# opencoral_moonlight.net
KiCad netlist of a schematic drawn in EAGLE
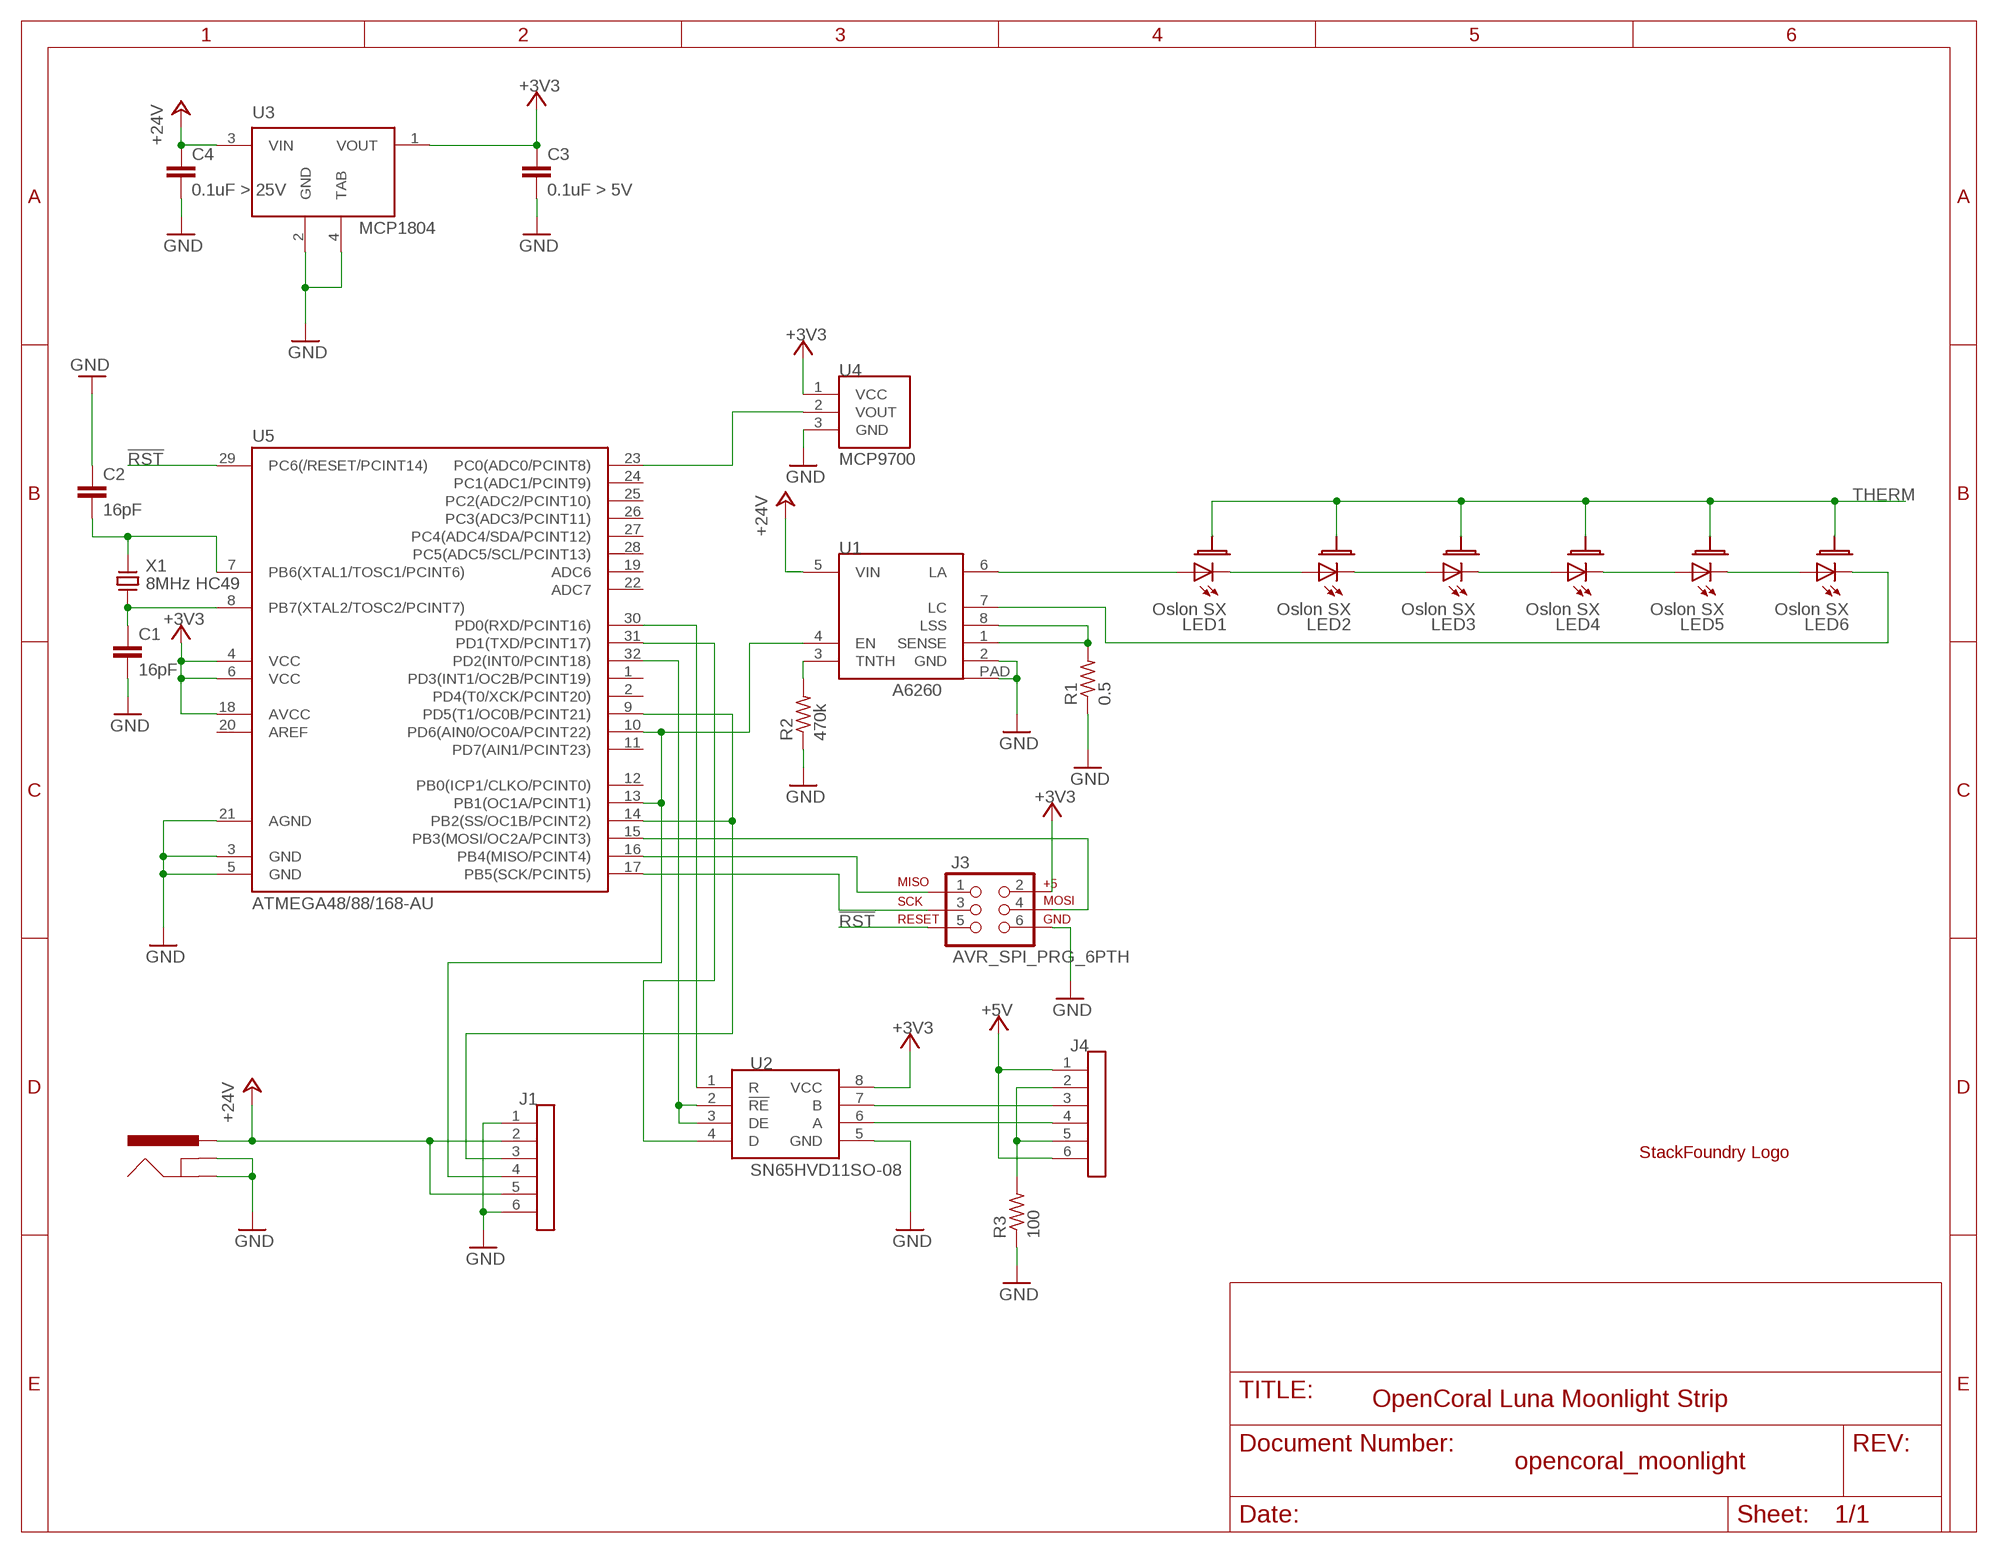
[diagram p0: schematic, sheet 1]

(export (version "E")
  (design (tool "Eeschema 10.0.6"))
  (components
    (comp (ref "C1")
      (value "16pF")
      (footprint "eagle-import:C0603")
      (libsource (lib "eagle-import") (part "C-EUC0603"))
    )
    (comp (ref "C2")
      (value "16pF")
      (footprint "eagle-import:C0603")
      (libsource (lib "eagle-import") (part "C-EUC0603"))
    )
    (comp (ref "C3")
      (value "0.1uF > 5V")
      (footprint "eagle-import:C0603")
      (libsource (lib "eagle-import") (part "C-EUC0603"))
    )
    (comp (ref "C4")
      (value "0.1uF > 25V")
      (footprint "eagle-import:C0603")
      (libsource (lib "eagle-import") (part "C-EUC0603"))
    )
    (comp (ref "J1")
      (value "RJ12")
      (footprint "eagle-import:A-2004-RJ12")
      (libsource (lib "eagle-import") (part "RJ12"))
    )
    (comp (ref "J2")
      (value "POWER_JACKPTH")
      (footprint "eagle-import:POWER_JACK_PTH")
      (libsource (lib "eagle-import") (part "POWER_JACKPTH"))
    )
    (comp (ref "J3")
      (value "AVR_SPI_PRG_6PTH")
      (footprint "eagle-import:2X3")
      (libsource (lib "eagle-import") (part "AVR_SPI_PRG_6PTH"))
    )
    (comp (ref "J4")
      (value "RJ12")
      (footprint "eagle-import:A-2004-RJ12")
      (libsource (lib "eagle-import") (part "RJ12"))
    )
    (comp (ref "LED1")
      (value "Oslon SX")
      (footprint "eagle-import:OSRAM_OSLON_SX")
      (libsource (lib "eagle-import") (part "LEDOSLON_SX"))
    )
    (comp (ref "LED2")
      (value "Oslon SX")
      (footprint "eagle-import:OSRAM_OSLON_SX")
      (libsource (lib "eagle-import") (part "LEDOSLON_SX"))
    )
    (comp (ref "LED3")
      (value "Oslon SX")
      (footprint "eagle-import:OSRAM_OSLON_SX")
      (libsource (lib "eagle-import") (part "LEDOSLON_SX"))
    )
    (comp (ref "LED4")
      (value "Oslon SX")
      (footprint "eagle-import:OSRAM_OSLON_SX")
      (libsource (lib "eagle-import") (part "LEDOSLON_SX"))
    )
    (comp (ref "LED5")
      (value "Oslon SX")
      (footprint "eagle-import:OSRAM_OSLON_SX")
      (libsource (lib "eagle-import") (part "LEDOSLON_SX"))
    )
    (comp (ref "LED6")
      (value "Oslon SX")
      (footprint "eagle-import:OSRAM_OSLON_SX")
      (libsource (lib "eagle-import") (part "LEDOSLON_SX"))
    )
    (comp (ref "LOGO1")
      (value "SFLOGO")
      (footprint "eagle-import:SFLOGO")
      (libsource (lib "eagle-import") (part "SFLOGO"))
    )
    (comp (ref "R1")
      (value "0.5")
      (footprint "eagle-import:R0805")
      (libsource (lib "eagle-import") (part "R-US_R0805"))
    )
    (comp (ref "R2")
      (value "470k")
      (footprint "eagle-import:R0603")
      (libsource (lib "eagle-import") (part "R-US_R0603"))
    )
    (comp (ref "R3")
      (value "100")
      (footprint "eagle-import:R0603")
      (libsource (lib "eagle-import") (part "R-US_R0603"))
    )
    (comp (ref "U1")
      (value "A6260")
      (footprint "eagle-import:ESOIC-8")
      (libsource (lib "eagle-import") (part "A6260"))
    )
    (comp (ref "U2")
      (value "SN65HVD11SO-08")
      (footprint "eagle-import:SO-08")
      (libsource (lib "eagle-import") (part "SN65HVD11SO-08"))
    )
    (comp (ref "U3")
      (value "MCP1804")
      (footprint "eagle-import:SOT223-3")
      (libsource (lib "eagle-import") (part "MCP1804"))
    )
    (comp (ref "U4")
      (value "MCP9700")
      (footprint "eagle-import:SOT23")
      (libsource (lib "eagle-import") (part "MCP9700"))
    )
    (comp (ref "U5")
      (value "ATMEGA48/88/168-AU")
      (footprint "eagle-import:TQFP32-08")
      (libsource (lib "eagle-import") (part "ATMEGA48/88/168-AU"))
    )
    (comp (ref "X1")
      (value "8MHz HC49")
      (footprint "eagle-import:HCM49")
      (libsource (lib "eagle-import") (part "HCM49_18.432M"))
    )
  )
  (nets
    (net (code "1") (name "+3V3") (class "Default")
      (node (ref "C3") (pin "1") (pinfunction "1_1") (pintype "passive"))
      (node (ref "J3") (pin "2") (pinfunction "2_2") (pintype "passive"))
      (node (ref "U2") (pin "8") (pinfunction "VCC_8") (pintype "bidirectional"))
      (node (ref "U3") (pin "1") (pinfunction "VOUT_1") (pintype "bidirectional"))
      (node (ref "U4") (pin "1") (pinfunction "VCC_1") (pintype "bidirectional"))
      (node (ref "U5") (pin "18") (pinfunction "AVCC_18") (pintype "passive"))
      (node (ref "U5") (pin "4") (pinfunction "VCC_4") (pintype "power_in"))
      (node (ref "U5") (pin "6") (pinfunction "VCC_6") (pintype "power_in"))
    )
    (net (code "2") (name "+5V") (class "Default")
      (node (ref "J4") (pin "1") (pinfunction "P$1_1") (pintype "bidirectional"))
      (node (ref "J4") (pin "6") (pinfunction "P$6_6") (pintype "bidirectional"))
    )
    (net (code "3") (name "+24V") (class "Default")
      (node (ref "C4") (pin "1") (pinfunction "1_1") (pintype "passive"))
      (node (ref "J1") (pin "2") (pinfunction "P$2_2") (pintype "bidirectional"))
      (node (ref "J1") (pin "5") (pinfunction "P$5_5") (pintype "bidirectional"))
      (node (ref "J2") (pin "PWR") (pinfunction "PWR_PWR") (pintype "bidirectional"))
      (node (ref "U1") (pin "5") (pinfunction "VIN_5") (pintype "bidirectional"))
      (node (ref "U3") (pin "3") (pinfunction "VIN_3") (pintype "bidirectional"))
    )
    (net (code "4") (name "/THERM") (class "Default")
      (node (ref "LED1") (pin "THERM") (pinfunction "THERM_THERM") (pintype "bidirectional"))
      (node (ref "LED2") (pin "THERM") (pinfunction "THERM_THERM") (pintype "bidirectional"))
      (node (ref "LED3") (pin "THERM") (pinfunction "THERM_THERM") (pintype "bidirectional"))
      (node (ref "LED4") (pin "THERM") (pinfunction "THERM_THERM") (pintype "bidirectional"))
      (node (ref "LED5") (pin "THERM") (pinfunction "THERM_THERM") (pintype "bidirectional"))
      (node (ref "LED6") (pin "THERM") (pinfunction "THERM_THERM") (pintype "bidirectional"))
    )
    (net (code "5") (name "/~{RST}") (class "Default")
      (node (ref "J3") (pin "5") (pinfunction "5_5") (pintype "passive"))
      (node (ref "U5") (pin "29") (pinfunction "PC6(/RESET/PCINT14)_29") (pintype "bidirectional"))
    )
    (net (code "6") (name "GND") (class "Default")
      (node (ref "C1") (pin "2") (pinfunction "2_2") (pintype "passive"))
      (node (ref "C2") (pin "1") (pinfunction "1_1") (pintype "passive"))
      (node (ref "C3") (pin "2") (pinfunction "2_2") (pintype "passive"))
      (node (ref "C4") (pin "2") (pinfunction "2_2") (pintype "passive"))
      (node (ref "J1") (pin "1") (pinfunction "P$1_1") (pintype "bidirectional"))
      (node (ref "J1") (pin "6") (pinfunction "P$6_6") (pintype "bidirectional"))
      (node (ref "J2") (pin "GND") (pinfunction "GND_GND") (pintype "bidirectional"))
      (node (ref "J2") (pin "GNDBREAK") (pinfunction "GNDBREAK_GNDBREAK") (pintype "bidirectional"))
      (node (ref "J3") (pin "6") (pinfunction "6_6") (pintype "passive"))
      (node (ref "R1") (pin "1") (pinfunction "1_1") (pintype "passive"))
      (node (ref "R2") (pin "1") (pinfunction "1_1") (pintype "passive"))
      (node (ref "R3") (pin "1") (pinfunction "1_1") (pintype "passive"))
      (node (ref "U1") (pin "2") (pinfunction "GND_2") (pintype "bidirectional"))
      (node (ref "U1") (pin "PAD") (pinfunction "PAD_PAD") (pintype "bidirectional"))
      (node (ref "U2") (pin "5") (pinfunction "GND_5") (pintype "bidirectional"))
      (node (ref "U3") (pin "2") (pinfunction "GND_2") (pintype "bidirectional"))
      (node (ref "U3") (pin "4") (pinfunction "TAB_4") (pintype "bidirectional"))
      (node (ref "U4") (pin "3") (pinfunction "GND_3") (pintype "bidirectional"))
      (node (ref "U5") (pin "21") (pinfunction "AGND_21") (pintype "power_in"))
      (node (ref "U5") (pin "3") (pinfunction "GND_3") (pintype "power_in"))
      (node (ref "U5") (pin "5") (pinfunction "GND_5") (pintype "power_in"))
    )
    (net (code "7") (name "Net-(J1-P$3)") (class "Default")
      (node (ref "J1") (pin "3") (pinfunction "P$3_3") (pintype "bidirectional"))
      (node (ref "U5") (pin "14") (pinfunction "PB2(SS/OC1B/PCINT2)_14") (pintype "bidirectional"))
      (node (ref "U5") (pin "9") (pinfunction "PD5(T1/OC0B/PCINT21)_9") (pintype "bidirectional"))
    )
    (net (code "8") (name "Net-(J1-P$4)") (class "Default")
      (node (ref "J1") (pin "4") (pinfunction "P$4_4") (pintype "bidirectional"))
      (node (ref "U1") (pin "4") (pinfunction "EN_4") (pintype "bidirectional"))
      (node (ref "U5") (pin "10") (pinfunction "PD6(AIN0/OC0A/PCINT22)_10") (pintype "bidirectional"))
      (node (ref "U5") (pin "13") (pinfunction "PB1(OC1A/PCINT1)_13") (pintype "bidirectional"))
    )
    (net (code "9") (name "Net-(J4-P$2)") (class "Default")
      (node (ref "J4") (pin "2") (pinfunction "P$2_2") (pintype "bidirectional"))
      (node (ref "J4") (pin "5") (pinfunction "P$5_5") (pintype "bidirectional"))
      (node (ref "R3") (pin "2") (pinfunction "2_2") (pintype "passive"))
    )
    (net (code "10") (name "Net-(J4-P$3)") (class "Default")
      (node (ref "J4") (pin "3") (pinfunction "P$3_3") (pintype "bidirectional"))
      (node (ref "U2") (pin "7") (pinfunction "B_7") (pintype "bidirectional"))
    )
    (net (code "11") (name "Net-(J4-P$4)") (class "Default")
      (node (ref "J4") (pin "4") (pinfunction "P$4_4") (pintype "bidirectional"))
      (node (ref "U2") (pin "6") (pinfunction "A_6") (pintype "bidirectional"))
    )
    (net (code "12") (name "Net-(LED1-PadC)") (class "Default")
      (node (ref "LED1") (pin "C") (pinfunction "C_C") (pintype "passive"))
      (node (ref "LED2") (pin "A") (pinfunction "A_A") (pintype "passive"))
    )
    (net (code "13") (name "Net-(LED2-PadC)") (class "Default")
      (node (ref "LED2") (pin "C") (pinfunction "C_C") (pintype "passive"))
      (node (ref "LED3") (pin "A") (pinfunction "A_A") (pintype "passive"))
    )
    (net (code "14") (name "Net-(LED3-PadC)") (class "Default")
      (node (ref "LED3") (pin "C") (pinfunction "C_C") (pintype "passive"))
      (node (ref "LED4") (pin "A") (pinfunction "A_A") (pintype "passive"))
    )
    (net (code "15") (name "Net-(LED4-PadC)") (class "Default")
      (node (ref "LED4") (pin "C") (pinfunction "C_C") (pintype "passive"))
      (node (ref "LED5") (pin "A") (pinfunction "A_A") (pintype "passive"))
    )
    (net (code "16") (name "Net-(LED5-PadC)") (class "Default")
      (node (ref "LED5") (pin "C") (pinfunction "C_C") (pintype "passive"))
      (node (ref "LED6") (pin "A") (pinfunction "A_A") (pintype "passive"))
    )
    (net (code "17") (name "Net-(U1-LA)") (class "Default")
      (node (ref "LED1") (pin "A") (pinfunction "A_A") (pintype "passive"))
      (node (ref "U1") (pin "6") (pinfunction "LA_6") (pintype "bidirectional"))
    )
    (net (code "18") (name "Net-(U1-LC)") (class "Default")
      (node (ref "LED6") (pin "C") (pinfunction "C_C") (pintype "passive"))
      (node (ref "U1") (pin "7") (pinfunction "LC_7") (pintype "bidirectional"))
    )
    (net (code "19") (name "Net-(U1-LSS)") (class "Default")
      (node (ref "R1") (pin "2") (pinfunction "2_2") (pintype "passive"))
      (node (ref "U1") (pin "1") (pinfunction "SENSE_1") (pintype "bidirectional"))
      (node (ref "U1") (pin "8") (pinfunction "LSS_8") (pintype "bidirectional"))
    )
    (net (code "20") (name "Net-(U1-TNTH)") (class "Default")
      (node (ref "R2") (pin "2") (pinfunction "2_2") (pintype "passive"))
      (node (ref "U1") (pin "3") (pinfunction "TNTH_3") (pintype "bidirectional"))
    )
    (net (code "21") (name "Net-(U2-D)") (class "Default")
      (node (ref "U2") (pin "4") (pinfunction "D_4") (pintype "bidirectional"))
      (node (ref "U5") (pin "31") (pinfunction "PD1(TXD/PCINT17)_31") (pintype "bidirectional"))
    )
    (net (code "22") (name "Net-(U2-DE)") (class "Default")
      (node (ref "U2") (pin "2") (pinfunction "~{RE}_2") (pintype "bidirectional"))
      (node (ref "U2") (pin "3") (pinfunction "DE_3") (pintype "bidirectional"))
      (node (ref "U5") (pin "32") (pinfunction "PD2(INT0/PCINT18)_32") (pintype "bidirectional"))
    )
    (net (code "23") (name "Net-(U2-R)") (class "Default")
      (node (ref "U2") (pin "1") (pinfunction "R_1") (pintype "bidirectional"))
      (node (ref "U5") (pin "30") (pinfunction "PD0(RXD/PCINT16)_30") (pintype "bidirectional"))
    )
    (net (code "24") (name "Net-(U4-VOUT)") (class "Default")
      (node (ref "U4") (pin "2") (pinfunction "VOUT_2") (pintype "bidirectional"))
      (node (ref "U5") (pin "23") (pinfunction "PC0(ADC0/PCINT8)_23") (pintype "bidirectional"))
    )
    (net (code "25") (name "Net-(U5-PB3(MOSI{slash}OC2A{slash}PCINT3))") (class "Default")
      (node (ref "J3") (pin "4") (pinfunction "4_4") (pintype "passive"))
      (node (ref "U5") (pin "15") (pinfunction "PB3(MOSI/OC2A/PCINT3)_15") (pintype "bidirectional"))
    )
    (net (code "26") (name "Net-(U5-PB4(MISO{slash}PCINT4))") (class "Default")
      (node (ref "J3") (pin "1") (pinfunction "1_1") (pintype "passive"))
      (node (ref "U5") (pin "16") (pinfunction "PB4(MISO/PCINT4)_16") (pintype "bidirectional"))
    )
    (net (code "27") (name "Net-(U5-PB5(SCK{slash}PCINT5))") (class "Default")
      (node (ref "J3") (pin "3") (pinfunction "3_3") (pintype "passive"))
      (node (ref "U5") (pin "17") (pinfunction "PB5(SCK/PCINT5)_17") (pintype "bidirectional"))
    )
    (net (code "28") (name "Net-(U5-PB6(XTAL1{slash}TOSC1{slash}PCINT6))") (class "Default")
      (node (ref "C2") (pin "2") (pinfunction "2_2") (pintype "passive"))
      (node (ref "U5") (pin "7") (pinfunction "PB6(XTAL1/TOSC1/PCINT6)_7") (pintype "bidirectional"))
      (node (ref "X1") (pin "P$1") (pinfunction "P$1_P$1") (pintype "bidirectional"))
    )
    (net (code "29") (name "Net-(U5-PB7(XTAL2{slash}TOSC2{slash}PCINT7))") (class "Default")
      (node (ref "C1") (pin "1") (pinfunction "1_1") (pintype "passive"))
      (node (ref "U5") (pin "8") (pinfunction "PB7(XTAL2/TOSC2/PCINT7)_8") (pintype "bidirectional"))
      (node (ref "X1") (pin "P$2") (pinfunction "P$2_P$2") (pintype "bidirectional"))
    )
    (net (code "30") (name "unconnected-(U5-ADC6-Pad19)") (class "Default")
      (node (ref "U5") (pin "19") (pinfunction "ADC6_19") (pintype "passive"))
    )
    (net (code "31") (name "unconnected-(U5-ADC7-Pad22)") (class "Default")
      (node (ref "U5") (pin "22") (pinfunction "ADC7_22") (pintype "passive"))
    )
    (net (code "32") (name "unconnected-(U5-AREF-Pad20)") (class "Default")
      (node (ref "U5") (pin "20") (pinfunction "AREF_20") (pintype "passive"))
    )
    (net (code "33") (name "unconnected-(U5-PB0(ICP1{slash}CLKO{slash}PCINT0)-Pad12)") (class "Default")
      (node (ref "U5") (pin "12") (pinfunction "PB0(ICP1/CLKO/PCINT0)_12") (pintype "bidirectional"))
    )
    (net (code "34") (name "unconnected-(U5-PC1(ADC1{slash}PCINT9)-Pad24)") (class "Default")
      (node (ref "U5") (pin "24") (pinfunction "PC1(ADC1/PCINT9)_24") (pintype "bidirectional"))
    )
    (net (code "35") (name "unconnected-(U5-PC2(ADC2{slash}PCINT10)-Pad25)") (class "Default")
      (node (ref "U5") (pin "25") (pinfunction "PC2(ADC2/PCINT10)_25") (pintype "bidirectional"))
    )
    (net (code "36") (name "unconnected-(U5-PC3(ADC3{slash}PCINT11)-Pad26)") (class "Default")
      (node (ref "U5") (pin "26") (pinfunction "PC3(ADC3/PCINT11)_26") (pintype "bidirectional"))
    )
    (net (code "37") (name "unconnected-(U5-PC4(ADC4{slash}SDA{slash}PCINT12)-Pad27)") (class "Default")
      (node (ref "U5") (pin "27") (pinfunction "PC4(ADC4/SDA/PCINT12)_27") (pintype "bidirectional"))
    )
    (net (code "38") (name "unconnected-(U5-PC5(ADC5{slash}SCL{slash}PCINT13)-Pad28)") (class "Default")
      (node (ref "U5") (pin "28") (pinfunction "PC5(ADC5/SCL/PCINT13)_28") (pintype "bidirectional"))
    )
    (net (code "39") (name "unconnected-(U5-PD3(INT1{slash}OC2B{slash}PCINT19)-Pad1)") (class "Default")
      (node (ref "U5") (pin "1") (pinfunction "PD3(INT1/OC2B/PCINT19)_1") (pintype "bidirectional"))
    )
    (net (code "40") (name "unconnected-(U5-PD4(T0{slash}XCK{slash}PCINT20)-Pad2)") (class "Default")
      (node (ref "U5") (pin "2") (pinfunction "PD4(T0/XCK/PCINT20)_2") (pintype "bidirectional"))
    )
    (net (code "41") (name "unconnected-(U5-PD7(AIN1{slash}PCINT23)-Pad11)") (class "Default")
      (node (ref "U5") (pin "11") (pinfunction "PD7(AIN1/PCINT23)_11") (pintype "bidirectional"))
    )
  )
)
